# timerboard.net
KiCad netlist of a schematic drawn in EAGLE
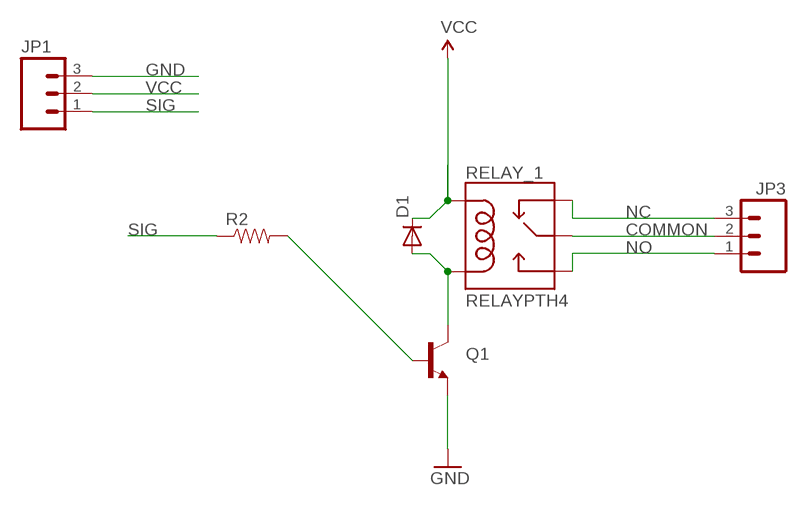
[diagram p0: schematic, sheet 1]

(export (version "E")
  (design (tool "Eeschema 10.0.6"))
  (components
    (comp (ref "D1")
      (value "DIODE1N4148")
      (footprint "eagle-import:DIODE-1N4148")
      (libsource (lib "eagle-import") (part "DIODE1N4148"))
    )
    (comp (ref "JP1")
      (value "M03PTH")
      (footprint "eagle-import:1X03")
      (libsource (lib "eagle-import") (part "M03PTH"))
    )
    (comp (ref "JP3")
      (value "M03-SCREW-5MM")
      (footprint "eagle-import:SCREWTERMINAL-5MM-3")
      (libsource (lib "eagle-import") (part "M03-SCREW-5MM"))
    )
    (comp (ref "Q1")
      (value "TRANSISTOR_NPNTO-92-AMMO")
      (footprint "eagle-import:TO-92-AMMO")
      (libsource (lib "eagle-import") (part "TRANSISTOR_NPNTO-92-AMMO"))
    )
    (comp (ref "R2")
      (value "RESISTORPTH-1/4W")
      (footprint "eagle-import:AXIAL-0.4")
      (libsource (lib "eagle-import") (part "RESISTORPTH-1/4W"))
    )
    (comp (ref "RELAY_1")
      (value "RELAYPTH4")
      (footprint "eagle-import:RELAY-JZC")
      (libsource (lib "eagle-import") (part "RELAYPTH4"))
    )
  )
  (nets
    (net (code "1") (name "/COMMON") (class "Default")
      (node (ref "JP3") (pin "2") (pinfunction "2_2") (pintype "passive"))
      (node (ref "RELAY_1") (pin "4") (pinfunction "MAIN_4") (pintype "bidirectional"))
    )
    (net (code "2") (name "/NC") (class "Default")
      (node (ref "JP3") (pin "3") (pinfunction "3_3") (pintype "passive"))
      (node (ref "RELAY_1") (pin "2") (pinfunction "NC_2") (pintype "bidirectional"))
    )
    (net (code "3") (name "/NO") (class "Default")
      (node (ref "JP3") (pin "1") (pinfunction "1_1") (pintype "passive"))
      (node (ref "RELAY_1") (pin "3") (pinfunction "NO_3") (pintype "bidirectional"))
    )
    (net (code "4") (name "/SIG") (class "Default")
      (node (ref "JP1") (pin "1") (pinfunction "1_1") (pintype "passive"))
      (node (ref "R2") (pin "P$1") (pinfunction "1_P$1") (pintype "passive"))
    )
    (net (code "5") (name "GND") (class "Default")
      (node (ref "JP1") (pin "3") (pinfunction "3_3") (pintype "passive"))
      (node (ref "Q1") (pin "1") (pinfunction "E_1") (pintype "passive"))
    )
    (net (code "6") (name "Net-(Q1-B)") (class "Default")
      (node (ref "Q1") (pin "2") (pinfunction "B_2") (pintype "passive"))
      (node (ref "R2") (pin "P$2") (pinfunction "2_P$2") (pintype "passive"))
    )
    (net (code "7") (name "Net-(Q1-C)") (class "Default")
      (node (ref "D1") (pin "A") (pinfunction "A_A") (pintype "passive"))
      (node (ref "Q1") (pin "3") (pinfunction "C_3") (pintype "passive"))
      (node (ref "RELAY_1") (pin "1") (pinfunction "COIL2_1") (pintype "bidirectional"))
    )
    (net (code "8") (name "VCC") (class "Default")
      (node (ref "D1") (pin "C") (pinfunction "C_C") (pintype "passive"))
      (node (ref "JP1") (pin "2") (pinfunction "2_2") (pintype "passive"))
      (node (ref "RELAY_1") (pin "5") (pinfunction "COIL1_5") (pintype "bidirectional"))
    )
  )
)
